# 1_RK3399_PowerPins.net
KiCad netlist of a schematic drawn in Altium Designer
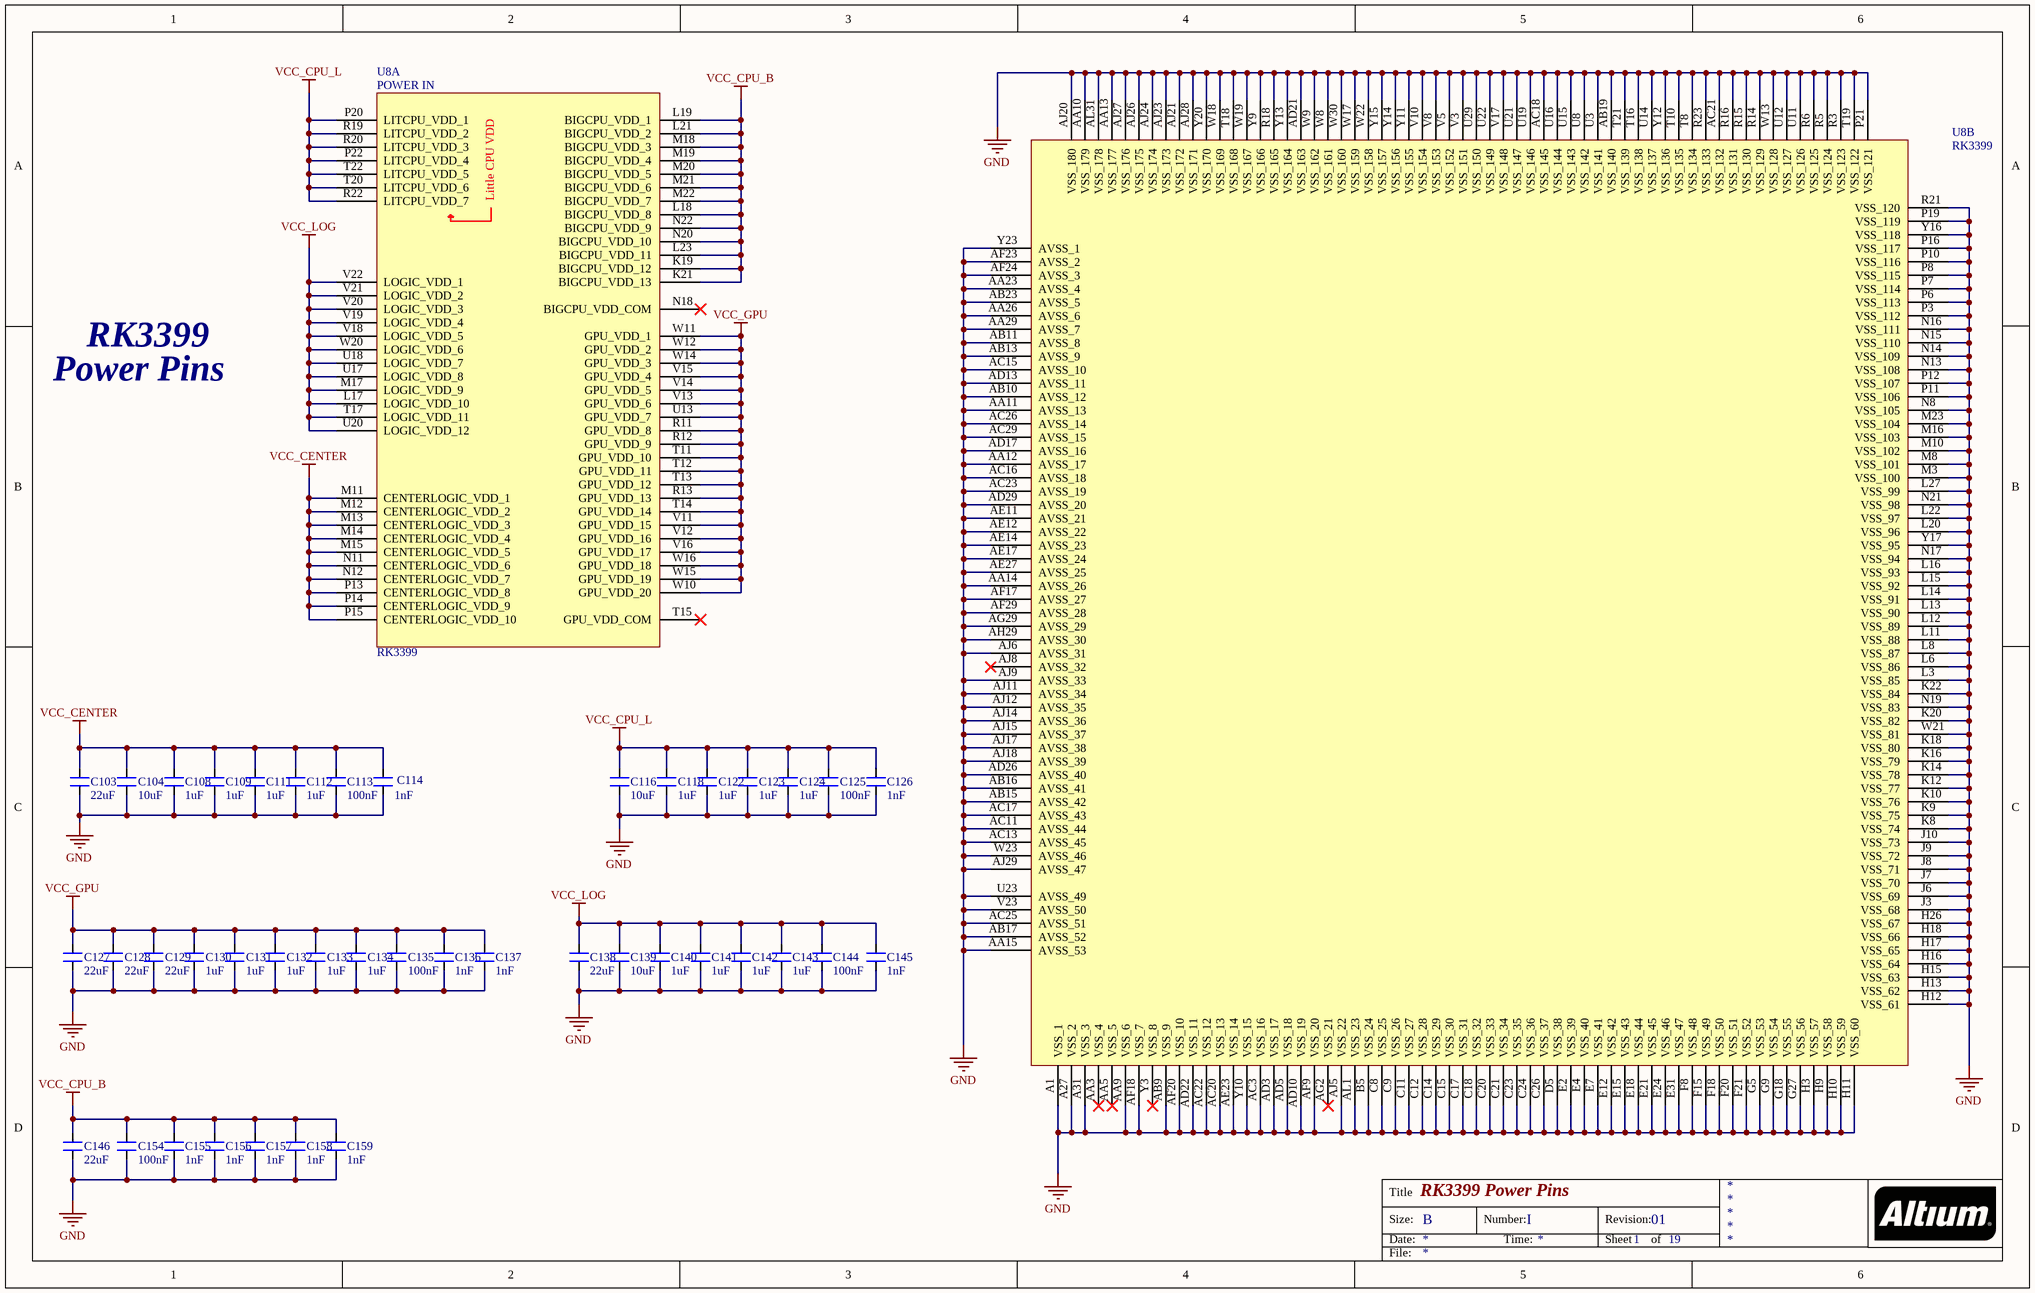
[diagram p0: [1] RK3399_PowerPins.SchDoc]

(export (version "E")
  (design (tool "Eeschema 10.0.6"))
  (components
    (comp (ref "C103")
      (value "22uF")
      (footprint "CAP_0603")
      (description "22µF ±20% 10V Ceramic Capacitor X5R 0603 (1608 Metric)")
      (fields
        (field (name "MANUFACTURER") "Murata Electronics")
        (field (name "MANUFACTURER PART NUMBER") "GRM188R61A226ME15D")
      )
      (libsource (lib "EsteemPCB_SOM_Course_intlib") (part "CAP_22uF-10V-20%-0603"))
    )
    (comp (ref "C104")
      (value "10uF")
      (footprint "CAP_0603")
      (description "10µF ±10% 25V Ceramic Capacitor X5R 0603 (1608 Metric)")
      (fields
        (field (name "MANUFACTURER") "Murata Electronics")
        (field (name "MANUFACTURER PART NUMBER") "GRM188R61E106KA73D")
      )
      (libsource (lib "EsteemPCB_SOM_Course_intlib") (part "CAP_10uF-25V-10%-0603"))
    )
    (comp (ref "C108")
      (value "1uF")
      (footprint "CAP_0201")
      (description "1µF ±20% 16V Ceramic Capacitor X5R 0201 (0603 Metric)")
      (fields
        (field (name "MANUFACTURER") "Samsung Electro-Mechanics")
        (field (name "MANUFACTURER PART NUMBER") "CL03A105MO3NRNH")
      )
      (libsource (lib "EsteemPCB_SOM_Course_intlib") (part "CAP_1uF-16V-10%-0201"))
    )
    (comp (ref "C109")
      (value "1uF")
      (footprint "CAP_0201")
      (description "1µF ±20% 16V Ceramic Capacitor X5R 0201 (0603 Metric)")
      (fields
        (field (name "MANUFACTURER") "Samsung Electro-Mechanics")
        (field (name "MANUFACTURER PART NUMBER") "CL03A105MO3NRNH")
      )
      (libsource (lib "EsteemPCB_SOM_Course_intlib") (part "CAP_1uF-16V-10%-0201"))
    )
    (comp (ref "C111")
      (value "1uF")
      (footprint "CAP_0201")
      (description "1µF ±20% 16V Ceramic Capacitor X5R 0201 (0603 Metric)")
      (fields
        (field (name "MANUFACTURER") "Samsung Electro-Mechanics")
        (field (name "MANUFACTURER PART NUMBER") "CL03A105MO3NRNH")
      )
      (libsource (lib "EsteemPCB_SOM_Course_intlib") (part "CAP_1uF-16V-10%-0201"))
    )
    (comp (ref "C112")
      (value "1uF")
      (footprint "CAP_0201")
      (description "1µF ±20% 16V Ceramic Capacitor X5R 0201 (0603 Metric)")
      (fields
        (field (name "MANUFACTURER") "Samsung Electro-Mechanics")
        (field (name "MANUFACTURER PART NUMBER") "CL03A105MO3NRNH")
      )
      (libsource (lib "EsteemPCB_SOM_Course_intlib") (part "CAP_1uF-16V-10%-0201"))
    )
    (comp (ref "C113")
      (value "100nF")
      (footprint "CAP_0201")
      (description "0.1µF ±10% 25V Ceramic Capacitor X5R 0201 (0603 Metric)")
      (fields
        (field (name "MANUFACTURER") "TDK Corporation")
        (field (name "MANUFACTURER PART NUMBER") "C0603X5R1E104K030BB")
      )
      (libsource (lib "EsteemPCB_SOM_Course_intlib") (part "CAP_100nF-25V-10%-0201"))
    )
    (comp (ref "C114")
      (value "1nF")
      (footprint "CAP_0201")
      (description "1000pF ±10% 16V Ceramic Capacitor X7R 0201 (0603 Metric)")
      (fields
        (field (name "MANUFACTURER") "Murata Electronics")
        (field (name "MANUFACTURER PART NUMBER") "GRM033R71C102KA01D")
      )
      (libsource (lib "EsteemPCB_SOM_Course_intlib") (part "CAP_1nF-16V-10%-0201"))
    )
    (comp (ref "C116")
      (value "10uF")
      (footprint "CAP_0603")
      (description "10µF ±10% 25V Ceramic Capacitor X5R 0603 (1608 Metric)")
      (fields
        (field (name "MANUFACTURER") "Murata Electronics")
        (field (name "MANUFACTURER PART NUMBER") "GRM188R61E106KA73D")
      )
      (libsource (lib "EsteemPCB_SOM_Course_intlib") (part "CAP_10uF-25V-10%-0603"))
    )
    (comp (ref "C118")
      (value "1uF")
      (footprint "CAP_0201")
      (description "1µF ±20% 16V Ceramic Capacitor X5R 0201 (0603 Metric)")
      (fields
        (field (name "MANUFACTURER") "Samsung Electro-Mechanics")
        (field (name "MANUFACTURER PART NUMBER") "CL03A105MO3NRNH")
      )
      (libsource (lib "EsteemPCB_SOM_Course_intlib") (part "CAP_1uF-16V-10%-0201"))
    )
    (comp (ref "C122")
      (value "1uF")
      (footprint "CAP_0201")
      (description "1µF ±20% 16V Ceramic Capacitor X5R 0201 (0603 Metric)")
      (fields
        (field (name "MANUFACTURER") "Samsung Electro-Mechanics")
        (field (name "MANUFACTURER PART NUMBER") "CL03A105MO3NRNH")
      )
      (libsource (lib "EsteemPCB_SOM_Course_intlib") (part "CAP_1uF-16V-10%-0201"))
    )
    (comp (ref "C123")
      (value "1uF")
      (footprint "CAP_0201")
      (description "1µF ±20% 16V Ceramic Capacitor X5R 0201 (0603 Metric)")
      (fields
        (field (name "MANUFACTURER") "Samsung Electro-Mechanics")
        (field (name "MANUFACTURER PART NUMBER") "CL03A105MO3NRNH")
      )
      (libsource (lib "EsteemPCB_SOM_Course_intlib") (part "CAP_1uF-16V-10%-0201"))
    )
    (comp (ref "C124")
      (value "1uF")
      (footprint "CAP_0201")
      (description "1µF ±20% 16V Ceramic Capacitor X5R 0201 (0603 Metric)")
      (fields
        (field (name "MANUFACTURER") "Samsung Electro-Mechanics")
        (field (name "MANUFACTURER PART NUMBER") "CL03A105MO3NRNH")
      )
      (libsource (lib "EsteemPCB_SOM_Course_intlib") (part "CAP_1uF-16V-10%-0201"))
    )
    (comp (ref "C125")
      (value "100nF")
      (footprint "CAP_0201")
      (description "0.1µF ±10% 25V Ceramic Capacitor X5R 0201 (0603 Metric)")
      (fields
        (field (name "MANUFACTURER") "TDK Corporation")
        (field (name "MANUFACTURER PART NUMBER") "C0603X5R1E104K030BB")
      )
      (libsource (lib "EsteemPCB_SOM_Course_intlib") (part "CAP_100nF-25V-10%-0201"))
    )
    (comp (ref "C126")
      (value "1nF")
      (footprint "CAP_0201")
      (description "1000pF ±10% 16V Ceramic Capacitor X7R 0201 (0603 Metric)")
      (fields
        (field (name "MANUFACTURER") "Murata Electronics")
        (field (name "MANUFACTURER PART NUMBER") "GRM033R71C102KA01D")
      )
      (libsource (lib "EsteemPCB_SOM_Course_intlib") (part "CAP_1nF-16V-10%-0201"))
    )
    (comp (ref "C127")
      (value "22uF")
      (footprint "CAP_0603")
      (description "22µF ±20% 10V Ceramic Capacitor X5R 0603 (1608 Metric)")
      (fields
        (field (name "MANUFACTURER") "Murata Electronics")
        (field (name "MANUFACTURER PART NUMBER") "GRM188R61A226ME15D")
      )
      (libsource (lib "EsteemPCB_SOM_Course_intlib") (part "CAP_22uF-10V-20%-0603"))
    )
    (comp (ref "C128")
      (value "22uF")
      (footprint "CAP_0603")
      (description "22µF ±20% 10V Ceramic Capacitor X5R 0603 (1608 Metric)")
      (fields
        (field (name "MANUFACTURER") "Murata Electronics")
        (field (name "MANUFACTURER PART NUMBER") "GRM188R61A226ME15D")
      )
      (libsource (lib "EsteemPCB_SOM_Course_intlib") (part "CAP_22uF-10V-20%-0603"))
    )
    (comp (ref "C129")
      (value "22uF")
      (footprint "CAP_0603")
      (description "22µF ±20% 10V Ceramic Capacitor X5R 0603 (1608 Metric)")
      (fields
        (field (name "MANUFACTURER") "Murata Electronics")
        (field (name "MANUFACTURER PART NUMBER") "GRM188R61A226ME15D")
      )
      (libsource (lib "EsteemPCB_SOM_Course_intlib") (part "CAP_22uF-10V-20%-0603"))
    )
    (comp (ref "C130")
      (value "1uF")
      (footprint "CAP_0201")
      (description "1µF ±20% 16V Ceramic Capacitor X5R 0201 (0603 Metric)")
      (fields
        (field (name "MANUFACTURER") "Samsung Electro-Mechanics")
        (field (name "MANUFACTURER PART NUMBER") "CL03A105MO3NRNH")
      )
      (libsource (lib "EsteemPCB_SOM_Course_intlib") (part "CAP_1uF-16V-10%-0201"))
    )
    (comp (ref "C131")
      (value "1uF")
      (footprint "CAP_0201")
      (description "1µF ±20% 16V Ceramic Capacitor X5R 0201 (0603 Metric)")
      (fields
        (field (name "MANUFACTURER") "Samsung Electro-Mechanics")
        (field (name "MANUFACTURER PART NUMBER") "CL03A105MO3NRNH")
      )
      (libsource (lib "EsteemPCB_SOM_Course_intlib") (part "CAP_1uF-16V-10%-0201"))
    )
    (comp (ref "C132")
      (value "1uF")
      (footprint "CAP_0201")
      (description "1µF ±20% 16V Ceramic Capacitor X5R 0201 (0603 Metric)")
      (fields
        (field (name "MANUFACTURER") "Samsung Electro-Mechanics")
        (field (name "MANUFACTURER PART NUMBER") "CL03A105MO3NRNH")
      )
      (libsource (lib "EsteemPCB_SOM_Course_intlib") (part "CAP_1uF-16V-10%-0201"))
    )
    (comp (ref "C133")
      (value "1uF")
      (footprint "CAP_0201")
      (description "1µF ±20% 16V Ceramic Capacitor X5R 0201 (0603 Metric)")
      (fields
        (field (name "MANUFACTURER") "Samsung Electro-Mechanics")
        (field (name "MANUFACTURER PART NUMBER") "CL03A105MO3NRNH")
      )
      (libsource (lib "EsteemPCB_SOM_Course_intlib") (part "CAP_1uF-16V-10%-0201"))
    )
    (comp (ref "C134")
      (value "1uF")
      (footprint "CAP_0201")
      (description "1µF ±20% 16V Ceramic Capacitor X5R 0201 (0603 Metric)")
      (fields
        (field (name "MANUFACTURER") "Samsung Electro-Mechanics")
        (field (name "MANUFACTURER PART NUMBER") "CL03A105MO3NRNH")
      )
      (libsource (lib "EsteemPCB_SOM_Course_intlib") (part "CAP_1uF-16V-10%-0201"))
    )
    (comp (ref "C135")
      (value "100nF")
      (footprint "CAP_0201")
      (description "0.1µF ±10% 25V Ceramic Capacitor X5R 0201 (0603 Metric)")
      (fields
        (field (name "MANUFACTURER") "TDK Corporation")
        (field (name "MANUFACTURER PART NUMBER") "C0603X5R1E104K030BB")
      )
      (libsource (lib "EsteemPCB_SOM_Course_intlib") (part "CAP_100nF-25V-10%-0201"))
    )
    (comp (ref "C136")
      (value "1nF")
      (footprint "CAP_0201")
      (description "1000pF ±10% 16V Ceramic Capacitor X7R 0201 (0603 Metric)")
      (fields
        (field (name "MANUFACTURER") "Murata Electronics")
        (field (name "MANUFACTURER PART NUMBER") "GRM033R71C102KA01D")
      )
      (libsource (lib "EsteemPCB_SOM_Course_intlib") (part "CAP_1nF-16V-10%-0201"))
    )
    (comp (ref "C137")
      (value "1nF")
      (footprint "CAP_0201")
      (description "1000pF ±10% 16V Ceramic Capacitor X7R 0201 (0603 Metric)")
      (fields
        (field (name "MANUFACTURER") "Murata Electronics")
        (field (name "MANUFACTURER PART NUMBER") "GRM033R71C102KA01D")
      )
      (libsource (lib "EsteemPCB_SOM_Course_intlib") (part "CAP_1nF-16V-10%-0201"))
    )
    (comp (ref "C138")
      (value "22uF")
      (footprint "CAP_0603")
      (description "22µF ±20% 10V Ceramic Capacitor X5R 0603 (1608 Metric)")
      (fields
        (field (name "MANUFACTURER") "Murata Electronics")
        (field (name "MANUFACTURER PART NUMBER") "GRM188R61A226ME15D")
      )
      (libsource (lib "EsteemPCB_SOM_Course_intlib") (part "CAP_22uF-10V-20%-0603"))
    )
    (comp (ref "C139")
      (value "10uF")
      (footprint "CAP_0603")
      (description "10µF ±10% 25V Ceramic Capacitor X5R 0603 (1608 Metric)")
      (fields
        (field (name "MANUFACTURER") "Murata Electronics")
        (field (name "MANUFACTURER PART NUMBER") "GRM188R61E106KA73D")
      )
      (libsource (lib "EsteemPCB_SOM_Course_intlib") (part "CAP_10uF-25V-10%-0603"))
    )
    (comp (ref "C140")
      (value "1uF")
      (footprint "CAP_0201")
      (description "1µF ±20% 16V Ceramic Capacitor X5R 0201 (0603 Metric)")
      (fields
        (field (name "MANUFACTURER") "Samsung Electro-Mechanics")
        (field (name "MANUFACTURER PART NUMBER") "CL03A105MO3NRNH")
      )
      (libsource (lib "EsteemPCB_SOM_Course_intlib") (part "CAP_1uF-16V-10%-0201"))
    )
    (comp (ref "C141")
      (value "1uF")
      (footprint "CAP_0201")
      (description "1µF ±20% 16V Ceramic Capacitor X5R 0201 (0603 Metric)")
      (fields
        (field (name "MANUFACTURER") "Samsung Electro-Mechanics")
        (field (name "MANUFACTURER PART NUMBER") "CL03A105MO3NRNH")
      )
      (libsource (lib "EsteemPCB_SOM_Course_intlib") (part "CAP_1uF-16V-10%-0201"))
    )
    (comp (ref "C142")
      (value "1uF")
      (footprint "CAP_0201")
      (description "1µF ±20% 16V Ceramic Capacitor X5R 0201 (0603 Metric)")
      (fields
        (field (name "MANUFACTURER") "Samsung Electro-Mechanics")
        (field (name "MANUFACTURER PART NUMBER") "CL03A105MO3NRNH")
      )
      (libsource (lib "EsteemPCB_SOM_Course_intlib") (part "CAP_1uF-16V-10%-0201"))
    )
    (comp (ref "C143")
      (value "1uF")
      (footprint "CAP_0201")
      (description "1µF ±20% 16V Ceramic Capacitor X5R 0201 (0603 Metric)")
      (fields
        (field (name "MANUFACTURER") "Samsung Electro-Mechanics")
        (field (name "MANUFACTURER PART NUMBER") "CL03A105MO3NRNH")
      )
      (libsource (lib "EsteemPCB_SOM_Course_intlib") (part "CAP_1uF-16V-10%-0201"))
    )
    (comp (ref "C144")
      (value "100nF")
      (footprint "CAP_0201")
      (description "0.1µF ±10% 25V Ceramic Capacitor X5R 0201 (0603 Metric)")
      (fields
        (field (name "MANUFACTURER") "TDK Corporation")
        (field (name "MANUFACTURER PART NUMBER") "C0603X5R1E104K030BB")
      )
      (libsource (lib "EsteemPCB_SOM_Course_intlib") (part "CAP_100nF-25V-10%-0201"))
    )
    (comp (ref "C145")
      (value "1nF")
      (footprint "CAP_0201")
      (description "1000pF ±10% 16V Ceramic Capacitor X7R 0201 (0603 Metric)")
      (fields
        (field (name "MANUFACTURER") "Murata Electronics")
        (field (name "MANUFACTURER PART NUMBER") "GRM033R71C102KA01D")
      )
      (libsource (lib "EsteemPCB_SOM_Course_intlib") (part "CAP_1nF-16V-10%-0201"))
    )
    (comp (ref "C146")
      (value "22uF")
      (footprint "CAP_0603")
      (description "22µF ±20% 10V Ceramic Capacitor X5R 0603 (1608 Metric)")
      (fields
        (field (name "MANUFACTURER") "Murata Electronics")
        (field (name "MANUFACTURER PART NUMBER") "GRM188R61A226ME15D")
      )
      (libsource (lib "EsteemPCB_SOM_Course_intlib") (part "CAP_22uF-10V-20%-0603"))
    )
    (comp (ref "C154")
      (value "100nF")
      (footprint "CAP_0201")
      (description "0.1µF ±10% 25V Ceramic Capacitor X5R 0201 (0603 Metric)")
      (fields
        (field (name "MANUFACTURER") "TDK Corporation")
        (field (name "MANUFACTURER PART NUMBER") "C0603X5R1E104K030BB")
      )
      (libsource (lib "EsteemPCB_SOM_Course_intlib") (part "CAP_100nF-25V-10%-0201"))
    )
    (comp (ref "C155")
      (value "1nF")
      (footprint "CAP_0201")
      (description "1000pF ±10% 16V Ceramic Capacitor X7R 0201 (0603 Metric)")
      (fields
        (field (name "MANUFACTURER") "Murata Electronics")
        (field (name "MANUFACTURER PART NUMBER") "GRM033R71C102KA01D")
      )
      (libsource (lib "EsteemPCB_SOM_Course_intlib") (part "CAP_1nF-16V-10%-0201"))
    )
    (comp (ref "C156")
      (value "1nF")
      (footprint "CAP_0201")
      (description "1000pF ±10% 16V Ceramic Capacitor X7R 0201 (0603 Metric)")
      (fields
        (field (name "MANUFACTURER") "Murata Electronics")
        (field (name "MANUFACTURER PART NUMBER") "GRM033R71C102KA01D")
      )
      (libsource (lib "EsteemPCB_SOM_Course_intlib") (part "CAP_1nF-16V-10%-0201"))
    )
    (comp (ref "C157")
      (value "1nF")
      (footprint "CAP_0201")
      (description "1000pF ±10% 16V Ceramic Capacitor X7R 0201 (0603 Metric)")
      (fields
        (field (name "MANUFACTURER") "Murata Electronics")
        (field (name "MANUFACTURER PART NUMBER") "GRM033R71C102KA01D")
      )
      (libsource (lib "EsteemPCB_SOM_Course_intlib") (part "CAP_1nF-16V-10%-0201"))
    )
    (comp (ref "C158")
      (value "1nF")
      (footprint "CAP_0201")
      (description "1000pF ±10% 16V Ceramic Capacitor X7R 0201 (0603 Metric)")
      (fields
        (field (name "MANUFACTURER") "Murata Electronics")
        (field (name "MANUFACTURER PART NUMBER") "GRM033R71C102KA01D")
      )
      (libsource (lib "EsteemPCB_SOM_Course_intlib") (part "CAP_1nF-16V-10%-0201"))
    )
    (comp (ref "C159")
      (value "1nF")
      (footprint "CAP_0201")
      (description "1000pF ±10% 16V Ceramic Capacitor X7R 0201 (0603 Metric)")
      (fields
        (field (name "MANUFACTURER") "Murata Electronics")
        (field (name "MANUFACTURER PART NUMBER") "GRM033R71C102KA01D")
      )
      (libsource (lib "EsteemPCB_SOM_Course_intlib") (part "CAP_1nF-16V-10%-0201"))
    )
    (comp (ref "U8")
      (value "RK3399")
      (footprint "FBGA828_23_826X826")
      (description "RK3399 is a low power, high performance processor for computing, personal mobile.")
      (fields (field (name "MANUFACTURER") "Rockchip"))
      (libsource (lib "EsteemPCB_SOM_Course_intlib") (part "IC_RK3399-FCBGA828"))
    )
  )
  (nets
    (net (code "1") (name "GND") (class "Default")
      (node (ref "C103") (pin "1") (pinfunction "1_1") (pintype "passive"))
      (node (ref "C104") (pin "1") (pinfunction "1_1") (pintype "passive"))
      (node (ref "C108") (pin "1") (pinfunction "1_1") (pintype "passive"))
      (node (ref "C109") (pin "1") (pinfunction "1_1") (pintype "passive"))
      (node (ref "C111") (pin "1") (pinfunction "1_1") (pintype "passive"))
      (node (ref "C112") (pin "1") (pinfunction "1_1") (pintype "passive"))
      (node (ref "C113") (pin "1") (pinfunction "1_1") (pintype "passive"))
      (node (ref "C114") (pin "1") (pinfunction "1_1") (pintype "passive"))
      (node (ref "C116") (pin "1") (pinfunction "1_1") (pintype "passive"))
      (node (ref "C118") (pin "1") (pinfunction "1_1") (pintype "passive"))
      (node (ref "C122") (pin "1") (pinfunction "1_1") (pintype "passive"))
      (node (ref "C123") (pin "1") (pinfunction "1_1") (pintype "passive"))
      (node (ref "C124") (pin "1") (pinfunction "1_1") (pintype "passive"))
      (node (ref "C125") (pin "1") (pinfunction "1_1") (pintype "passive"))
      (node (ref "C126") (pin "1") (pinfunction "1_1") (pintype "passive"))
      (node (ref "C127") (pin "1") (pinfunction "1_1") (pintype "passive"))
      (node (ref "C128") (pin "1") (pinfunction "1_1") (pintype "passive"))
      (node (ref "C129") (pin "1") (pinfunction "1_1") (pintype "passive"))
      (node (ref "C130") (pin "1") (pinfunction "1_1") (pintype "passive"))
      (node (ref "C131") (pin "1") (pinfunction "1_1") (pintype "passive"))
      (node (ref "C132") (pin "1") (pinfunction "1_1") (pintype "passive"))
      (node (ref "C133") (pin "1") (pinfunction "1_1") (pintype "passive"))
      (node (ref "C134") (pin "1") (pinfunction "1_1") (pintype "passive"))
      (node (ref "C135") (pin "1") (pinfunction "1_1") (pintype "passive"))
      (node (ref "C136") (pin "1") (pinfunction "1_1") (pintype "passive"))
      (node (ref "C137") (pin "1") (pinfunction "1_1") (pintype "passive"))
      (node (ref "C138") (pin "1") (pinfunction "1_1") (pintype "passive"))
      (node (ref "C139") (pin "1") (pinfunction "1_1") (pintype "passive"))
      (node (ref "C140") (pin "1") (pinfunction "1_1") (pintype "passive"))
      (node (ref "C141") (pin "1") (pinfunction "1_1") (pintype "passive"))
      (node (ref "C142") (pin "1") (pinfunction "1_1") (pintype "passive"))
      (node (ref "C143") (pin "1") (pinfunction "1_1") (pintype "passive"))
      (node (ref "C144") (pin "1") (pinfunction "1_1") (pintype "passive"))
      (node (ref "C145") (pin "1") (pinfunction "1_1") (pintype "passive"))
      (node (ref "C146") (pin "1") (pinfunction "1_1") (pintype "passive"))
      (node (ref "C154") (pin "1") (pinfunction "1_1") (pintype "passive"))
      (node (ref "C155") (pin "1") (pinfunction "1_1") (pintype "passive"))
      (node (ref "C156") (pin "1") (pinfunction "1_1") (pintype "passive"))
      (node (ref "C157") (pin "1") (pinfunction "1_1") (pintype "passive"))
      (node (ref "C158") (pin "1") (pinfunction "1_1") (pintype "passive"))
      (node (ref "C159") (pin "1") (pinfunction "1_1") (pintype "passive"))
      (node (ref "U8") (pin "A1") (pinfunction "VSS_1_A1") (pintype "passive"))
      (node (ref "U8") (pin "A27") (pinfunction "VSS_2_A27") (pintype "passive"))
      (node (ref "U8") (pin "A31") (pinfunction "VSS_3_A31") (pintype "passive"))
      (node (ref "U8") (pin "AA10") (pinfunction "VSS_179_AA10") (pintype "passive"))
      (node (ref "U8") (pin "AA11") (pinfunction "AVSS_13_AA11") (pintype "passive"))
      (node (ref "U8") (pin "AA12") (pinfunction "AVSS_17_AA12") (pintype "passive"))
      (node (ref "U8") (pin "AA13") (pinfunction "VSS_177_AA13") (pintype "passive"))
      (node (ref "U8") (pin "AA14") (pinfunction "AVSS_26_AA14") (pintype "passive"))
      (node (ref "U8") (pin "AA15") (pinfunction "AVSS_53_AA15") (pintype "passive"))
      (node (ref "U8") (pin "AA23") (pinfunction "AVSS_4_AA23") (pintype "passive"))
      (node (ref "U8") (pin "AA26") (pinfunction "AVSS_6_AA26") (pintype "passive"))
      (node (ref "U8") (pin "AA29") (pinfunction "AVSS_7_AA29") (pintype "passive"))
      (node (ref "U8") (pin "AA9") (pinfunction "VSS_6_AA9") (pintype "passive"))
      (node (ref "U8") (pin "AB10") (pinfunction "AVSS_12_AB10") (pintype "passive"))
      (node (ref "U8") (pin "AB11") (pinfunction "AVSS_8_AB11") (pintype "passive"))
      (node (ref "U8") (pin "AB13") (pinfunction "AVSS_9_AB13") (pintype "passive"))
      (node (ref "U8") (pin "AB15") (pinfunction "AVSS_42_AB15") (pintype "passive"))
      (node (ref "U8") (pin "AB16") (pinfunction "AVSS_41_AB16") (pintype "passive"))
      (node (ref "U8") (pin "AB17") (pinfunction "AVSS_52_AB17") (pintype "passive"))
      (node (ref "U8") (pin "AB19") (pinfunction "VSS_140_AB19") (pintype "passive"))
      (node (ref "U8") (pin "AB23") (pinfunction "AVSS_5_AB23") (pintype "passive"))
      (node (ref "U8") (pin "AB9") (pinfunction "VSS_9_AB9") (pintype "passive"))
      (node (ref "U8") (pin "AC11") (pinfunction "AVSS_44_AC11") (pintype "passive"))
      (node (ref "U8") (pin "AC13") (pinfunction "AVSS_45_AC13") (pintype "passive"))
      (node (ref "U8") (pin "AC15") (pinfunction "AVSS_10_AC15") (pintype "passive"))
      (node (ref "U8") (pin "AC16") (pinfunction "AVSS_18_AC16") (pintype "passive"))
      (node (ref "U8") (pin "AC17") (pinfunction "AVSS_43_AC17") (pintype "passive"))
      (node (ref "U8") (pin "AC18") (pinfunction "VSS_145_AC18") (pintype "passive"))
      (node (ref "U8") (pin "AC20") (pinfunction "VSS_13_AC20") (pintype "passive"))
      (node (ref "U8") (pin "AC21") (pinfunction "VSS_132_AC21") (pintype "passive"))
      (node (ref "U8") (pin "AC22") (pinfunction "VSS_12_AC22") (pintype "passive"))
      (node (ref "U8") (pin "AC23") (pinfunction "AVSS_19_AC23") (pintype "passive"))
      (node (ref "U8") (pin "AC25") (pinfunction "AVSS_51_AC25") (pintype "passive"))
      (node (ref "U8") (pin "AC26") (pinfunction "AVSS_14_AC26") (pintype "passive"))
      (node (ref "U8") (pin "AC29") (pinfunction "AVSS_15_AC29") (pintype "passive"))
      (node (ref "U8") (pin "AC3") (pinfunction "VSS_16_AC3") (pintype "passive"))
      (node (ref "U8") (pin "AD10") (pinfunction "VSS_19_AD10") (pintype "passive"))
      (node (ref "U8") (pin "AD13") (pinfunction "AVSS_11_AD13") (pintype "passive"))
      (node (ref "U8") (pin "AD17") (pinfunction "AVSS_16_AD17") (pintype "passive"))
      (node (ref "U8") (pin "AD21") (pinfunction "VSS_163_AD21") (pintype "passive"))
      (node (ref "U8") (pin "AD22") (pinfunction "VSS_11_AD22") (pintype "passive"))
      (node (ref "U8") (pin "AD26") (pinfunction "AVSS_40_AD26") (pintype "passive"))
      (node (ref "U8") (pin "AD29") (pinfunction "AVSS_20_AD29") (pintype "passive"))
      (node (ref "U8") (pin "AD3") (pinfunction "VSS_17_AD3") (pintype "passive"))
      (node (ref "U8") (pin "AD5") (pinfunction "VSS_18_AD5") (pintype "passive"))
      (node (ref "U8") (pin "AE11") (pinfunction "AVSS_21_AE11") (pintype "passive"))
      (node (ref "U8") (pin "AE12") (pinfunction "AVSS_22_AE12") (pintype "passive"))
      (node (ref "U8") (pin "AE14") (pinfunction "AVSS_23_AE14") (pintype "passive"))
      (node (ref "U8") (pin "AE17") (pinfunction "AVSS_24_AE17") (pintype "passive"))
      (node (ref "U8") (pin "AE23") (pinfunction "VSS_14_AE23") (pintype "passive"))
      (node (ref "U8") (pin "AE27") (pinfunction "AVSS_25_AE27") (pintype "passive"))
      (node (ref "U8") (pin "AF17") (pinfunction "AVSS_27_AF17") (pintype "passive"))
      (node (ref "U8") (pin "AF18") (pinfunction "VSS_7_AF18") (pintype "passive"))
      (node (ref "U8") (pin "AF20") (pinfunction "VSS_10_AF20") (pintype "passive"))
      (node (ref "U8") (pin "AF23") (pinfunction "AVSS_2_AF23") (pintype "passive"))
      (node (ref "U8") (pin "AF24") (pinfunction "AVSS_3_AF24") (pintype "passive"))
      (node (ref "U8") (pin "AF29") (pinfunction "AVSS_28_AF29") (pintype "passive"))
      (node (ref "U8") (pin "AF9") (pinfunction "VSS_20_AF9") (pintype "passive"))
      (node (ref "U8") (pin "AG29") (pinfunction "AVSS_29_AG29") (pintype "passive"))
      (node (ref "U8") (pin "AH29") (pinfunction "AVSS_30_AH29") (pintype "passive"))
      (node (ref "U8") (pin "AJ11") (pinfunction "AVSS_34_AJ11") (pintype "passive"))
      (node (ref "U8") (pin "AJ12") (pinfunction "AVSS_35_AJ12") (pintype "passive"))
      (node (ref "U8") (pin "AJ14") (pinfunction "AVSS_36_AJ14") (pintype "passive"))
      (node (ref "U8") (pin "AJ15") (pinfunction "AVSS_37_AJ15") (pintype "passive"))
      (node (ref "U8") (pin "AJ17") (pinfunction "AVSS_38_AJ17") (pintype "passive"))
      (node (ref "U8") (pin "AJ18") (pinfunction "AVSS_39_AJ18") (pintype "passive"))
      (node (ref "U8") (pin "AJ20") (pinfunction "VSS_180_AJ20") (pintype "passive"))
      (node (ref "U8") (pin "AJ21") (pinfunction "VSS_172_AJ21") (pintype "passive"))
      (node (ref "U8") (pin "AJ23") (pinfunction "VSS_173_AJ23") (pintype "passive"))
      (node (ref "U8") (pin "AJ24") (pinfunction "VSS_174_AJ24") (pintype "passive"))
      (node (ref "U8") (pin "AJ26") (pinfunction "VSS_175_AJ26") (pintype "passive"))
      (node (ref "U8") (pin "AJ27") (pinfunction "VSS_176_AJ27") (pintype "passive"))
      (node (ref "U8") (pin "AJ28") (pinfunction "VSS_171_AJ28") (pintype "passive"))
      (node (ref "U8") (pin "AJ29") (pinfunction "AVSS_47_AJ29") (pintype "passive"))
      (node (ref "U8") (pin "AJ5") (pinfunction "VSS_22_AJ5") (pintype "passive"))
      (node (ref "U8") (pin "AJ6") (pinfunction "AVSS_31_AJ6") (pintype "passive"))
      (node (ref "U8") (pin "AJ9") (pinfunction "AVSS_33_AJ9") (pintype "passive"))
      (node (ref "U8") (pin "AL1") (pinfunction "VSS_23_AL1") (pintype "passive"))
      (node (ref "U8") (pin "AL31") (pinfunction "VSS_178_AL31") (pintype "passive"))
      (node (ref "U8") (pin "B5") (pinfunction "VSS_24_B5") (pintype "passive"))
      (node (ref "U8") (pin "C11") (pinfunction "VSS_27_C11") (pintype "passive"))
      (node (ref "U8") (pin "C12") (pinfunction "VSS_28_C12") (pintype "passive"))
      (node (ref "U8") (pin "C14") (pinfunction "VSS_29_C14") (pintype "passive"))
      (node (ref "U8") (pin "C15") (pinfunction "VSS_30_C15") (pintype "passive"))
      (node (ref "U8") (pin "C17") (pinfunction "VSS_31_C17") (pintype "passive"))
      (node (ref "U8") (pin "C18") (pinfunction "VSS_32_C18") (pintype "passive"))
      (node (ref "U8") (pin "C20") (pinfunction "VSS_33_C20") (pintype "passive"))
      (node (ref "U8") (pin "C21") (pinfunction "VSS_34_C21") (pintype "passive"))
      (node (ref "U8") (pin "C23") (pinfunction "VSS_35_C23") (pintype "passive"))
      (node (ref "U8") (pin "C24") (pinfunction "VSS_36_C24") (pintype "passive"))
      (node (ref "U8") (pin "C26") (pinfunction "VSS_37_C26") (pintype "passive"))
      (node (ref "U8") (pin "C8") (pinfunction "VSS_25_C8") (pintype "passive"))
      (node (ref "U8") (pin "C9") (pinfunction "VSS_26_C9") (pintype "passive"))
      (node (ref "U8") (pin "D5") (pinfunction "VSS_38_D5") (pintype "passive"))
      (node (ref "U8") (pin "E12") (pinfunction "VSS_42_E12") (pintype "passive"))
      (node (ref "U8") (pin "E15") (pinfunction "VSS_43_E15") (pintype "passive"))
      (node (ref "U8") (pin "E18") (pinfunction "VSS_44_E18") (pintype "passive"))
      (node (ref "U8") (pin "E2") (pinfunction "VSS_39_E2") (pintype "passive"))
      (node (ref "U8") (pin "E21") (pinfunction "VSS_45_E21") (pintype "passive"))
      (node (ref "U8") (pin "E24") (pinfunction "VSS_46_E24") (pintype "passive"))
      (node (ref "U8") (pin "E31") (pinfunction "VSS_47_E31") (pintype "passive"))
      (node (ref "U8") (pin "E4") (pinfunction "VSS_40_E4") (pintype "passive"))
      (node (ref "U8") (pin "E7") (pinfunction "VSS_41_E7") (pintype "passive"))
      (node (ref "U8") (pin "F15") (pinfunction "VSS_49_F15") (pintype "passive"))
      (node (ref "U8") (pin "F18") (pinfunction "VSS_50_F18") (pintype "passive"))
      (node (ref "U8") (pin "F20") (pinfunction "VSS_51_F20") (pintype "passive"))
      (node (ref "U8") (pin "F21") (pinfunction "VSS_52_F21") (pintype "passive"))
      (node (ref "U8") (pin "F8") (pinfunction "VSS_48_F8") (pintype "passive"))
      (node (ref "U8") (pin "G18") (pinfunction "VSS_55_G18") (pintype "passive"))
      (node (ref "U8") (pin "G27") (pinfunction "VSS_56_G27") (pintype "passive"))
      (node (ref "U8") (pin "G5") (pinfunction "VSS_53_G5") (pintype "passive"))
      (node (ref "U8") (pin "G9") (pinfunction "VSS_54_G9") (pintype "passive"))
      (node (ref "U8") (pin "H10") (pinfunction "VSS_59_H10") (pintype "passive"))
      (node (ref "U8") (pin "H11") (pinfunction "VSS_60_H11") (pintype "passive"))
      (node (ref "U8") (pin "H12") (pinfunction "VSS_61_H12") (pintype "passive"))
      (node (ref "U8") (pin "H13") (pinfunction "VSS_62_H13") (pintype "passive"))
      (node (ref "U8") (pin "H15") (pinfunction "VSS_63_H15") (pintype "passive"))
      (node (ref "U8") (pin "H16") (pinfunction "VSS_64_H16") (pintype "passive"))
      (node (ref "U8") (pin "H17") (pinfunction "VSS_65_H17") (pintype "passive"))
      (node (ref "U8") (pin "H18") (pinfunction "VSS_66_H18") (pintype "passive"))
      (node (ref "U8") (pin "H26") (pinfunction "VSS_67_H26") (pintype "passive"))
      (node (ref "U8") (pin "H3") (pinfunction "VSS_57_H3") (pintype "passive"))
      (node (ref "U8") (pin "H9") (pinfunction "VSS_58_H9") (pintype "passive"))
      (node (ref "U8") (pin "J10") (pinfunction "VSS_73_J10") (pintype "passive"))
      (node (ref "U8") (pin "J3") (pinfunction "VSS_68_J3") (pintype "passive"))
      (node (ref "U8") (pin "J6") (pinfunction "VSS_69_J6") (pintype "passive"))
      (node (ref "U8") (pin "J7") (pinfunction "VSS_70_J7") (pintype "passive"))
      (node (ref "U8") (pin "J8") (pinfunction "VSS_71_J8") (pintype "passive"))
      (node (ref "U8") (pin "J9") (pinfunction "VSS_72_J9") (pintype "passive"))
      (node (ref "U8") (pin "K10") (pinfunction "VSS_76_K10") (pintype "passive"))
      (node (ref "U8") (pin "K12") (pinfunction "VSS_77_K12") (pintype "passive"))
      (node (ref "U8") (pin "K14") (pinfunction "VSS_78_K14") (pintype "passive"))
      (node (ref "U8") (pin "K16") (pinfunction "VSS_79_K16") (pintype "passive"))
      (node (ref "U8") (pin "K18") (pinfunction "VSS_80_K18") (pintype "passive"))
      (node (ref "U8") (pin "K20") (pinfunction "VSS_82_K20") (pintype "passive"))
      (node (ref "U8") (pin "K22") (pinfunction "VSS_84_K22") (pintype "passive"))
      (node (ref "U8") (pin "K8") (pinfunction "VSS_74_K8") (pintype "passive"))
      (node (ref "U8") (pin "K9") (pinfunction "VSS_75_K9") (pintype "passive"))
      (node (ref "U8") (pin "L11") (pinfunction "VSS_88_L11") (pintype "passive"))
      (node (ref "U8") (pin "L12") (pinfunction "VSS_89_L12") (pintype "passive"))
      (node (ref "U8") (pin "L13") (pinfunction "VSS_90_L13") (pintype "passive"))
      (node (ref "U8") (pin "L14") (pinfunction "VSS_91_L14") (pintype "passive"))
      (node (ref "U8") (pin "L15") (pinfunction "VSS_92_L15") (pintype "passive"))
      (node (ref "U8") (pin "L16") (pinfunction "VSS_93_L16") (pintype "passive"))
      (node (ref "U8") (pin "L20") (pinfunction "VSS_96_L20") (pintype "passive"))
      (node (ref "U8") (pin "L22") (pinfunction "VSS_97_L22") (pintype "passive"))
      (node (ref "U8") (pin "L27") (pinfunction "VSS_99_L27") (pintype "passive"))
      (node (ref "U8") (pin "L3") (pinfunction "VSS_85_L3") (pintype "passive"))
      (node (ref "U8") (pin "L6") (pinfunction "VSS_86_L6") (pintype "passive"))
      (node (ref "U8") (pin "L8") (pinfunction "VSS_87_L8") (pintype "passive"))
      (node (ref "U8") (pin "M10") (pinfunction "VSS_102_M10") (pintype "passive"))
      (node (ref "U8") (pin "M16") (pinfunction "VSS_103_M16") (pintype "passive"))
      (node (ref "U8") (pin "M23") (pinfunction "VSS_104_M23") (pintype "passive"))
      (node (ref "U8") (pin "M3") (pinfunction "VSS_100_M3") (pintype "passive"))
      (node (ref "U8") (pin "M8") (pinfunction "VSS_101_M8") (pintype "passive"))
      (node (ref "U8") (pin "N13") (pinfunction "VSS_108_N13") (pintype "passive"))
      (node (ref "U8") (pin "N14") (pinfunction "VSS_109_N14") (pintype "passive"))
      (node (ref "U8") (pin "N15") (pinfunction "VSS_110_N15") (pintype "passive"))
      (node (ref "U8") (pin "N16") (pinfunction "VSS_111_N16") (pintype "passive"))
      (node (ref "U8") (pin "N17") (pinfunction "VSS_94_N17") (pintype "passive"))
      (node (ref "U8") (pin "N19") (pinfunction "VSS_83_N19") (pintype "passive"))
      (node (ref "U8") (pin "N21") (pinfunction "VSS_98_N21") (pintype "passive"))
      (node (ref "U8") (pin "N8") (pinfunction "VSS_105_N8") (pintype "passive"))
      (node (ref "U8") (pin "P10") (pinfunction "VSS_116_P10") (pintype "passive"))
      (node (ref "U8") (pin "P11") (pinfunction "VSS_106_P11") (pintype "passive"))
      (node (ref "U8") (pin "P12") (pinfunction "VSS_107_P12") (pintype "passive"))
      (node (ref "U8") (pin "P16") (pinfunction "VSS_117_P16") (pintype "passive"))
      (node (ref "U8") (pin "P19") (pinfunction "VSS_119_P19") (pintype "passive"))
      (node (ref "U8") (pin "P21") (pinfunction "VSS_121_P21") (pintype "passive"))
      (node (ref "U8") (pin "P3") (pinfunction "VSS_112_P3") (pintype "passive"))
      (node (ref "U8") (pin "P6") (pinfunction "VSS_113_P6") (pintype "passive"))
      (node (ref "U8") (pin "P7") (pinfunction "VSS_114_P7") (pintype "passive"))
      (node (ref "U8") (pin "P8") (pinfunction "VSS_115_P8") (pintype "passive"))
      (node (ref "U8") (pin "R14") (pinfunction "VSS_129_R14") (pintype "passive"))
      (node (ref "U8") (pin "R15") (pinfunction "VSS_130_R15") (pintype "passive"))
      (node (ref "U8") (pin "R16") (pinfunction "VSS_131_R16") (pintype "passive"))
      (node (ref "U8") (pin "R18") (pinfunction "VSS_165_R18") (pintype "passive"))
      (node (ref "U8") (pin "R21") (pinfunction "VSS_120_R21") (pintype "passive"))
      (node (ref "U8") (pin "R23") (pinfunction "VSS_133_R23") (pintype "passive"))
      (node (ref "U8") (pin "R3") (pinfunction "VSS_123_R3") (pintype "passive"))
      (node (ref "U8") (pin "R5") (pinfunction "VSS_124_R5") (pintype "passive"))
      (node (ref "U8") (pin "R6") (pinfunction "VSS_125_R6") (pintype "passive"))
      (node (ref "U8") (pin "T10") (pinfunction "VSS_135_T10") (pintype "passive"))
      (node (ref "U8") (pin "T16") (pinfunction "VSS_138_T16") (pintype "passive"))
      (node (ref "U8") (pin "T18") (pinfunction "VSS_168_T18") (pintype "passive"))
      (node (ref "U8") (pin "T19") (pinfunction "VSS_122_T19") (pintype "passive"))
      (node (ref "U8") (pin "T21") (pinfunction "VSS_139_T21") (pintype "passive"))
      (node (ref "U8") (pin "T8") (pinfunction "VSS_134_T8") (pintype "passive"))
      (node (ref "U8") (pin "U11") (pinfunction "VSS_126_U11") (pintype "passive"))
      (node (ref "U8") (pin "U12") (pinfunction "VSS_127_U12") (pintype "passive"))
      (node (ref "U8") (pin "U14") (pinfunction "VSS_137_U14") (pintype "passive"))
      (node (ref "U8") (pin "U15") (pinfunction "VSS_143_U15") (pintype "passive"))
      (node (ref "U8") (pin "U16") (pinfunction "VSS_144_U16") (pintype "passive"))
      (node (ref "U8") (pin "U19") (pinfunction "VSS_146_U19") (pintype "passive"))
      (node (ref "U8") (pin "U21") (pinfunction "VSS_147_U21") (pintype "passive"))
      (node (ref "U8") (pin "U22") (pinfunction "VSS_149_U22") (pintype "passive"))
      (node (ref "U8") (pin "U23") (pinfunction "AVSS_49_U23") (pintype "passive"))
      (node (ref "U8") (pin "U29") (pinfunction "VSS_150_U29") (pintype "passive"))
      (node (ref "U8") (pin "U3") (pinfunction "VSS_141_U3") (pintype "passive"))
      (node (ref "U8") (pin "U8") (pinfunction "VSS_142_U8") (pintype "passive"))
      (node (ref "U8") (pin "V10") (pinfunction "VSS_154_V10") (pintype "passive"))
      (node (ref "U8") (pin "V17") (pinfunction "VSS_148_V17") (pintype "passive"))
      (node (ref "U8") (pin "V23") (pinfunction "AVSS_50_V23") (pintype "passive"))
      (node (ref "U8") (pin "V3") (pinfunction "VSS_151_V3") (pintype "passive"))
      (node (ref "U8") (pin "V5") (pinfunction "VSS_152_V5") (pintype "passive"))
      (node (ref "U8") (pin "V8") (pinfunction "VSS_153_V8") (pintype "passive"))
      (node (ref "U8") (pin "W13") (pinfunction "VSS_128_W13") (pintype "passive"))
      (node (ref "U8") (pin "W17") (pinfunction "VSS_159_W17") (pintype "passive"))
      (node (ref "U8") (pin "W18") (pinfunction "VSS_169_W18") (pintype "passive"))
      (node (ref "U8") (pin "W19") (pinfunction "VSS_167_W19") (pintype "passive"))
      (node (ref "U8") (pin "W21") (pinfunction "VSS_81_W21") (pintype "passive"))
      (node (ref "U8") (pin "W22") (pinfunction "VSS_158_W22") (pintype "passive"))
      (node (ref "U8") (pin "W23") (pinfunction "AVSS_46_W23") (pintype "passive"))
      (node (ref "U8") (pin "W30") (pinfunction "VSS_160_W30") (pintype "passive"))
      (node (ref "U8") (pin "W8") (pinfunction "VSS_161_W8") (pintype "passive"))
      (node (ref "U8") (pin "W9") (pinfunction "VSS_162_W9") (pintype "passive"))
      (node (ref "U8") (pin "Y10") (pinfunction "VSS_15_Y10") (pintype "passive"))
      (node (ref "U8") (pin "Y11") (pinfunction "VSS_155_Y11") (pintype "passive"))
      (node (ref "U8") (pin "Y12") (pinfunction "VSS_136_Y12") (pintype "passive"))
      (node (ref "U8") (pin "Y13") (pinfunction "VSS_164_Y13") (pintype "passive"))
      (node (ref "U8") (pin "Y14") (pinfunction "VSS_156_Y14") (pintype "passive"))
      (node (ref "U8") (pin "Y15") (pinfunction "VSS_157_Y15") (pintype "passive"))
      (node (ref "U8") (pin "Y16") (pinfunction "VSS_118_Y16") (pintype "passive"))
      (node (ref "U8") (pin "Y17") (pinfunction "VSS_95_Y17") (pintype "passive"))
      (node (ref "U8") (pin "Y20") (pinfunction "VSS_170_Y20") (pintype "passive"))
      (node (ref "U8") (pin "Y23") (pinfunction "AVSS_1_Y23") (pintype "passive"))
      (node (ref "U8") (pin "Y9") (pinfunction "VSS_166_Y9") (pintype "passive"))
    )
    (net (code "2") (name "VCC_CENTER") (class "Default")
      (node (ref "C103") (pin "2") (pinfunction "2_2") (pintype "passive"))
      (node (ref "C104") (pin "2") (pinfunction "2_2") (pintype "passive"))
      (node (ref "C108") (pin "2") (pinfunction "2_2") (pintype "passive"))
      (node (ref "C109") (pin "2") (pinfunction "2_2") (pintype "passive"))
      (node (ref "C111") (pin "2") (pinfunction "2_2") (pintype "passive"))
      (node (ref "C112") (pin "2") (pinfunction "2_2") (pintype "passive"))
      (node (ref "C113") (pin "2") (pinfunction "2_2") (pintype "passive"))
      (node (ref "C114") (pin "2") (pinfunction "2_2") (pintype "passive"))
      (node (ref "U8") (pin "M11") (pinfunction "CENTERLOGIC_VDD_1_M11") (pintype "passive"))
      (node (ref "U8") (pin "M12") (pinfunction "CENTERLOGIC_VDD_2_M12") (pintype "passive"))
      (node (ref "U8") (pin "M13") (pinfunction "CENTERLOGIC_VDD_3_M13") (pintype "passive"))
      (node (ref "U8") (pin "M14") (pinfunction "CENTERLOGIC_VDD_4_M14") (pintype "passive"))
      (node (ref "U8") (pin "M15") (pinfunction "CENTERLOGIC_VDD_5_M15") (pintype "passive"))
      (node (ref "U8") (pin "N11") (pinfunction "CENTERLOGIC_VDD_6_N11") (pintype "passive"))
      (node (ref "U8") (pin "N12") (pinfunction "CENTERLOGIC_VDD_7_N12") (pintype "passive"))
      (node (ref "U8") (pin "P13") (pinfunction "CENTERLOGIC_VDD_8_P13") (pintype "passive"))
      (node (ref "U8") (pin "P14") (pinfunction "CENTERLOGIC_VDD_9_P14") (pintype "passive"))
      (node (ref "U8") (pin "P15") (pinfunction "CENTERLOGIC_VDD_10_P15") (pintype "passive"))
    )
    (net (code "3") (name "VCC_CPU_B") (class "Default")
      (node (ref "C146") (pin "2") (pinfunction "2_2") (pintype "passive"))
      (node (ref "C154") (pin "2") (pinfunction "2_2") (pintype "passive"))
      (node (ref "C155") (pin "2") (pinfunction "2_2") (pintype "passive"))
      (node (ref "C156") (pin "2") (pinfunction "2_2") (pintype "passive"))
      (node (ref "C157") (pin "2") (pinfunction "2_2") (pintype "passive"))
      (node (ref "C158") (pin "2") (pinfunction "2_2") (pintype "passive"))
      (node (ref "C159") (pin "2") (pinfunction "2_2") (pintype "passive"))
      (node (ref "U8") (pin "K19") (pinfunction "BIGCPU_VDD_12_K19") (pintype "passive"))
      (node (ref "U8") (pin "K21") (pinfunction "BIGCPU_VDD_13_K21") (pintype "passive"))
      (node (ref "U8") (pin "L18") (pinfunction "BIGCPU_VDD_8_L18") (pintype "passive"))
      (node (ref "U8") (pin "L19") (pinfunction "BIGCPU_VDD_1_L19") (pintype "passive"))
      (node (ref "U8") (pin "L21") (pinfunction "BIGCPU_VDD_2_L21") (pintype "passive"))
      (node (ref "U8") (pin "L23") (pinfunction "BIGCPU_VDD_11_L23") (pintype "passive"))
      (node (ref "U8") (pin "M18") (pinfunction "BIGCPU_VDD_3_M18") (pintype "passive"))
      (node (ref "U8") (pin "M19") (pinfunction "BIGCPU_VDD_4_M19") (pintype "passive"))
      (node (ref "U8") (pin "M20") (pinfunction "BIGCPU_VDD_5_M20") (pintype "passive"))
      (node (ref "U8") (pin "M21") (pinfunction "BIGCPU_VDD_6_M21") (pintype "passive"))
      (node (ref "U8") (pin "M22") (pinfunction "BIGCPU_VDD_7_M22") (pintype "passive"))
      (node (ref "U8") (pin "N20") (pinfunction "BIGCPU_VDD_10_N20") (pintype "passive"))
      (node (ref "U8") (pin "N22") (pinfunction "BIGCPU_VDD_9_N22") (pintype "passive"))
    )
    (net (code "4") (name "VCC_CPU_L") (class "Default")
      (node (ref "C116") (pin "2") (pinfunction "2_2") (pintype "passive"))
      (node (ref "C118") (pin "2") (pinfunction "2_2") (pintype "passive"))
      (node (ref "C122") (pin "2") (pinfunction "2_2") (pintype "passive"))
      (node (ref "C123") (pin "2") (pinfunction "2_2") (pintype "passive"))
      (node (ref "C124") (pin "2") (pinfunction "2_2") (pintype "passive"))
      (node (ref "C125") (pin "2") (pinfunction "2_2") (pintype "passive"))
      (node (ref "C126") (pin "2") (pinfunction "2_2") (pintype "passive"))
      (node (ref "U8") (pin "P20") (pinfunction "LITCPU_VDD_1_P20") (pintype "passive"))
      (node (ref "U8") (pin "P22") (pinfunction "LITCPU_VDD_4_P22") (pintype "passive"))
      (node (ref "U8") (pin "R19") (pinfunction "LITCPU_VDD_2_R19") (pintype "passive"))
      (node (ref "U8") (pin "R20") (pinfunction "LITCPU_VDD_3_R20") (pintype "passive"))
      (node (ref "U8") (pin "R22") (pinfunction "LITCPU_VDD_7_R22") (pintype "passive"))
      (node (ref "U8") (pin "T20") (pinfunction "LITCPU_VDD_6_T20") (pintype "passive"))
      (node (ref "U8") (pin "T22") (pinfunction "LITCPU_VDD_5_T22") (pintype "passive"))
    )
    (net (code "5") (name "VCC_GPU") (class "Default")
      (node (ref "C127") (pin "2") (pinfunction "2_2") (pintype "passive"))
      (node (ref "C128") (pin "2") (pinfunction "2_2") (pintype "passive"))
      (node (ref "C129") (pin "2") (pinfunction "2_2") (pintype "passive"))
      (node (ref "C130") (pin "2") (pinfunction "2_2") (pintype "passive"))
      (node (ref "C131") (pin "2") (pinfunction "2_2") (pintype "passive"))
      (node (ref "C132") (pin "2") (pinfunction "2_2") (pintype "passive"))
      (node (ref "C133") (pin "2") (pinfunction "2_2") (pintype "passive"))
      (node (ref "C134") (pin "2") (pinfunction "2_2") (pintype "passive"))
      (node (ref "C135") (pin "2") (pinfunction "2_2") (pintype "passive"))
      (node (ref "C136") (pin "2") (pinfunction "2_2") (pintype "passive"))
      (node (ref "C137") (pin "2") (pinfunction "2_2") (pintype "passive"))
      (node (ref "U8") (pin "R11") (pinfunction "GPU_VDD_8_R11") (pintype "passive"))
      (node (ref "U8") (pin "R12") (pinfunction "GPU_VDD_9_R12") (pintype "passive"))
      (node (ref "U8") (pin "R13") (pinfunction "GPU_VDD_13_R13") (pintype "passive"))
      (node (ref "U8") (pin "T11") (pinfunction "GPU_VDD_10_T11") (pintype "passive"))
      (node (ref "U8") (pin "T12") (pinfunction "GPU_VDD_11_T12") (pintype "passive"))
      (node (ref "U8") (pin "T13") (pinfunction "GPU_VDD_12_T13") (pintype "passive"))
      (node (ref "U8") (pin "T14") (pinfunction "GPU_VDD_14_T14") (pintype "passive"))
      (node (ref "U8") (pin "U13") (pinfunction "GPU_VDD_7_U13") (pintype "passive"))
      (node (ref "U8") (pin "V11") (pinfunction "GPU_VDD_15_V11") (pintype "passive"))
      (node (ref "U8") (pin "V12") (pinfunction "GPU_VDD_16_V12") (pintype "passive"))
      (node (ref "U8") (pin "V13") (pinfunction "GPU_VDD_6_V13") (pintype "passive"))
      (node (ref "U8") (pin "V14") (pinfunction "GPU_VDD_5_V14") (pintype "passive"))
      (node (ref "U8") (pin "V15") (pinfunction "GPU_VDD_4_V15") (pintype "passive"))
      (node (ref "U8") (pin "V16") (pinfunction "GPU_VDD_17_V16") (pintype "passive"))
      (node (ref "U8") (pin "W10") (pinfunction "GPU_VDD_20_W10") (pintype "passive"))
      (node (ref "U8") (pin "W11") (pinfunction "GPU_VDD_1_W11") (pintype "passive"))
      (node (ref "U8") (pin "W12") (pinfunction "GPU_VDD_2_W12") (pintype "passive"))
      (node (ref "U8") (pin "W14") (pinfunction "GPU_VDD_3_W14") (pintype "passive"))
      (node (ref "U8") (pin "W15") (pinfunction "GPU_VDD_19_W15") (pintype "passive"))
      (node (ref "U8") (pin "W16") (pinfunction "GPU_VDD_18_W16") (pintype "passive"))
    )
    (net (code "6") (name "VCC_LOG") (class "Default")
      (node (ref "C138") (pin "2") (pinfunction "2_2") (pintype "passive"))
      (node (ref "C139") (pin "2") (pinfunction "2_2") (pintype "passive"))
      (node (ref "C140") (pin "2") (pinfunction "2_2") (pintype "passive"))
      (node (ref "C141") (pin "2") (pinfunction "2_2") (pintype "passive"))
      (node (ref "C142") (pin "2") (pinfunction "2_2") (pintype "passive"))
      (node (ref "C143") (pin "2") (pinfunction "2_2") (pintype "passive"))
      (node (ref "C144") (pin "2") (pinfunction "2_2") (pintype "passive"))
      (node (ref "C145") (pin "2") (pinfunction "2_2") (pintype "passive"))
      (node (ref "U8") (pin "L17") (pinfunction "LOGIC_VDD_10_L17") (pintype "passive"))
      (node (ref "U8") (pin "M17") (pinfunction "LOGIC_VDD_9_M17") (pintype "passive"))
      (node (ref "U8") (pin "T17") (pinfunction "LOGIC_VDD_11_T17") (pintype "passive"))
      (node (ref "U8") (pin "U17") (pinfunction "LOGIC_VDD_8_U17") (pintype "passive"))
      (node (ref "U8") (pin "U18") (pinfunction "LOGIC_VDD_7_U18") (pintype "passive"))
      (node (ref "U8") (pin "U20") (pinfunction "LOGIC_VDD_12_U20") (pintype "passive"))
      (node (ref "U8") (pin "V18") (pinfunction "LOGIC_VDD_5_V18") (pintype "passive"))
      (node (ref "U8") (pin "V19") (pinfunction "LOGIC_VDD_4_V19") (pintype "passive"))
      (node (ref "U8") (pin "V20") (pinfunction "LOGIC_VDD_3_V20") (pintype "passive"))
      (node (ref "U8") (pin "V21") (pinfunction "LOGIC_VDD_2_V21") (pintype "passive"))
      (node (ref "U8") (pin "V22") (pinfunction "LOGIC_VDD_1_V22") (pintype "passive"))
      (node (ref "U8") (pin "W20") (pinfunction "LOGIC_VDD_6_W20") (pintype "passive"))
    )
    (net (code "7") (name "unconnected-(U8A-BIGCPU_VDD_COM-PadN18)") (class "Default")
      (node (ref "U8") (pin "N18") (pinfunction "BIGCPU_VDD_COM_N18") (pintype "passive+no_connect"))
    )
    (net (code "8") (name "unconnected-(U8A-GPU_VDD_COM-PadT15)") (class "Default")
      (node (ref "U8") (pin "T15") (pinfunction "GPU_VDD_COM_T15") (pintype "passive+no_connect"))
    )
    (net (code "9") (name "unconnected-(U8B-AVSS_32-PadAJ8)") (class "Default")
      (node (ref "U8") (pin "AJ8") (pinfunction "AVSS_32_AJ8") (pintype "passive+no_connect"))
    )
    (net (code "10") (name "unconnected-(U8B-VSS_4-PadAA3)") (class "Default")
      (node (ref "U8") (pin "AA3") (pinfunction "VSS_4_AA3") (pintype "passive+no_connect"))
    )
    (net (code "11") (name "unconnected-(U8B-VSS_5-PadAA5)") (class "Default")
      (node (ref "U8") (pin "AA5") (pinfunction "VSS_5_AA5") (pintype "passive+no_connect"))
    )
    (net (code "12") (name "unconnected-(U8B-VSS_8-PadY3)") (class "Default")
      (node (ref "U8") (pin "Y3") (pinfunction "VSS_8_Y3") (pintype "passive+no_connect"))
    )
    (net (code "13") (name "unconnected-(U8B-VSS_21-PadAG2)") (class "Default")
      (node (ref "U8") (pin "AG2") (pinfunction "VSS_21_AG2") (pintype "passive+no_connect"))
    )
  )
)
